# ee40_robot_final_p2.net
KiCad netlist of a schematic drawn in EAGLE
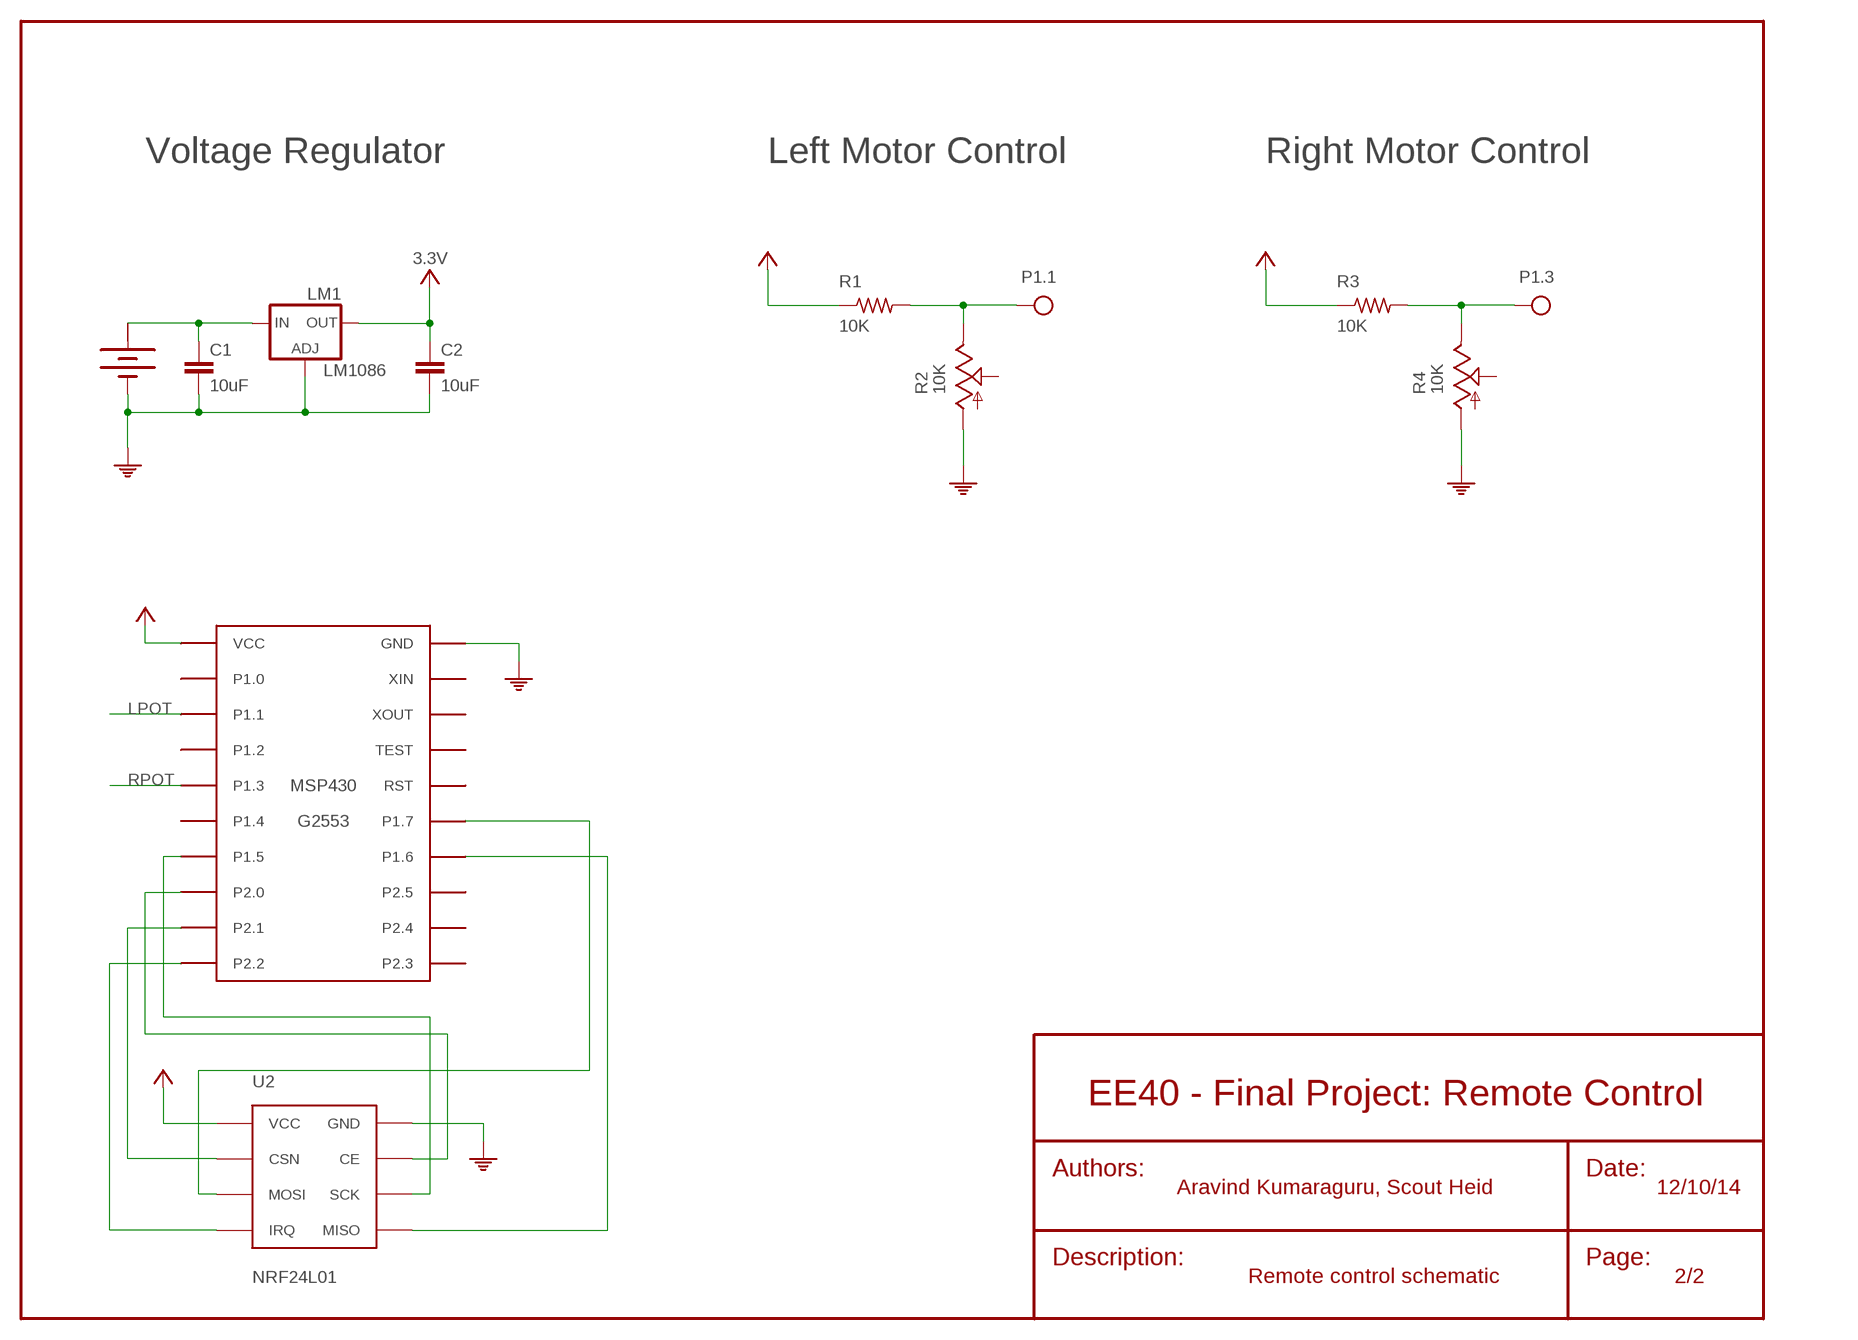
[diagram p0: schematic, sheet 1]

(export (version "E")
  (design (tool "Eeschema 10.0.6"))
  (components
    (comp (ref "BAT1")
      (value "9V D-CELL")
      (footprint "eagle-import:BATTERY")
      (libsource (lib "eagle-import") (part "BATTERY"))
    )
    (comp (ref "C1")
      (value "10uF")
      (footprint "eagle-import:C5B2.5")
      (libsource (lib "eagle-import") (part "C5/2.5"))
    )
    (comp (ref "C2")
      (value "10uF")
      (footprint "eagle-import:C5B2.5")
      (libsource (lib "eagle-import") (part "C5/2.5"))
    )
    (comp (ref "LM1")
      (value "LM1086")
      (footprint "eagle-import:TO220L1")
      (libsource (lib "eagle-import") (part "LM138-TL"))
    )
    (comp (ref "R1")
      (value "10K")
      (footprint "eagle-import:VMTA55")
      (libsource (lib "eagle-import") (part "R-US_VMTA55"))
    )
    (comp (ref "R2")
      (value "10K")
      (footprint "eagle-import:RJ9W")
      (libsource (lib "eagle-import") (part "TRIM_US-RJ9W"))
    )
    (comp (ref "R3")
      (value "10K")
      (footprint "eagle-import:VMTA55")
      (libsource (lib "eagle-import") (part "R-US_VMTA55"))
    )
    (comp (ref "R4")
      (value "10K")
      (footprint "eagle-import:RJ9W")
      (libsource (lib "eagle-import") (part "TRIM_US-RJ9W"))
    )
    (comp (ref "U1")
      (value "MSP430")
      (footprint "eagle-import:MSP430")
      (libsource (lib "eagle-import") (part "MSP430"))
    )
    (comp (ref "U2")
      (value "NRF24L01")
      (footprint "eagle-import:NRF24L01")
      (libsource (lib "eagle-import") (part "NRF24L01"))
    )
  )
  (nets
    (net (code "1") (name "/+") (class "Default")
      (node (ref "BAT1") (pin "+@1") (pinfunction "+_+@1") (pintype "power_in"))
    )
    (net (code "2") (name "3.3V") (class "Default")
      (node (ref "C2") (pin "1") (pinfunction "1_1") (pintype "passive"))
      (node (ref "LM1") (pin "2") (pinfunction "OUT_2") (pintype "passive"))
      (node (ref "R1") (pin "1") (pinfunction "1_1") (pintype "passive"))
      (node (ref "R3") (pin "1") (pinfunction "1_1") (pintype "passive"))
      (node (ref "U1") (pin "P$1") (pinfunction "VCC_P$1") (pintype "bidirectional"))
      (node (ref "U2") (pin "P$8") (pinfunction "VCC_P$8") (pintype "bidirectional"))
    )
    (net (code "3") (name "Net-(LM1-IN)") (class "Default")
      (node (ref "BAT1") (pin "+") (pinfunction "+_+") (pintype "power_in"))
      (node (ref "C1") (pin "1") (pinfunction "1_1") (pintype "passive"))
      (node (ref "LM1") (pin "3") (pinfunction "IN_3") (pintype "input"))
    )
    (net (code "4") (name "Net-(U1-P1.5)") (class "Default")
      (node (ref "U1") (pin "P$7") (pinfunction "P1.5_P$7") (pintype "bidirectional"))
      (node (ref "U2") (pin "P$7") (pinfunction "SCK_P$7") (pintype "bidirectional"))
    )
    (net (code "5") (name "Net-(U1-P1.6)") (class "Default")
      (node (ref "U1") (pin "P$14") (pinfunction "P1.6_P$14") (pintype "bidirectional"))
      (node (ref "U2") (pin "P$5") (pinfunction "MISO_P$5") (pintype "bidirectional"))
    )
    (net (code "6") (name "Net-(U1-P1.7)") (class "Default")
      (node (ref "U1") (pin "P$15") (pinfunction "P1.7_P$15") (pintype "bidirectional"))
      (node (ref "U2") (pin "P$6") (pinfunction "MOSI_P$6") (pintype "bidirectional"))
    )
    (net (code "7") (name "Net-(U1-P2.0)") (class "Default")
      (node (ref "U1") (pin "P$8") (pinfunction "P2.0_P$8") (pintype "bidirectional"))
      (node (ref "U2") (pin "P$1") (pinfunction "CE_P$1") (pintype "bidirectional"))
    )
    (net (code "8") (name "Net-(U1-P2.1)") (class "Default")
      (node (ref "U1") (pin "P$9") (pinfunction "P2.1_P$9") (pintype "bidirectional"))
      (node (ref "U2") (pin "P$2") (pinfunction "CSN_P$2") (pintype "bidirectional"))
    )
    (net (code "9") (name "Net-(U1-P2.2)") (class "Default")
      (node (ref "U1") (pin "P$10") (pinfunction "P2.2_P$10") (pintype "bidirectional"))
      (node (ref "U2") (pin "P$4") (pinfunction "IRQ_P$4") (pintype "bidirectional"))
    )
    (net (code "10") (name "P1.1") (class "Default")
      (node (ref "R1") (pin "2") (pinfunction "2_2") (pintype "passive"))
      (node (ref "R2") (pin "E") (pinfunction "E_E") (pintype "passive"))
      (node (ref "U1") (pin "P$3") (pinfunction "P1.1_P$3") (pintype "bidirectional"))
    )
    (net (code "11") (name "P1.3") (class "Default")
      (node (ref "R3") (pin "2") (pinfunction "2_2") (pintype "passive"))
      (node (ref "R4") (pin "E") (pinfunction "E_E") (pintype "passive"))
      (node (ref "U1") (pin "P$5") (pinfunction "P1.3_P$5") (pintype "bidirectional"))
    )
    (net (code "12") (name "PE") (class "Default")
      (node (ref "BAT1") (pin "-") (pinfunction "-_-") (pintype "power_in"))
      (node (ref "C1") (pin "2") (pinfunction "2_2") (pintype "passive"))
      (node (ref "C2") (pin "2") (pinfunction "2_2") (pintype "passive"))
      (node (ref "LM1") (pin "1") (pinfunction "ADJ_1") (pintype "input"))
      (node (ref "R2") (pin "A") (pinfunction "A_A") (pintype "passive"))
      (node (ref "R4") (pin "A") (pinfunction "A_A") (pintype "passive"))
      (node (ref "U1") (pin "P$20") (pinfunction "GND_P$20") (pintype "bidirectional"))
      (node (ref "U2") (pin "P$3") (pinfunction "GND_P$3") (pintype "bidirectional"))
    )
    (net (code "13") (name "unconnected-(R2-PadS)") (class "Default")
      (node (ref "R2") (pin "S") (pinfunction "S_S") (pintype "passive"))
    )
    (net (code "14") (name "unconnected-(R4-PadS)") (class "Default")
      (node (ref "R4") (pin "S") (pinfunction "S_S") (pintype "passive"))
    )
    (net (code "15") (name "unconnected-(U1-P1.0-PadP$2)") (class "Default")
      (node (ref "U1") (pin "P$2") (pinfunction "P1.0_P$2") (pintype "bidirectional"))
    )
    (net (code "16") (name "unconnected-(U1-P1.2-PadP$4)") (class "Default")
      (node (ref "U1") (pin "P$4") (pinfunction "P1.2_P$4") (pintype "bidirectional"))
    )
    (net (code "17") (name "unconnected-(U1-P1.4-PadP$6)") (class "Default")
      (node (ref "U1") (pin "P$6") (pinfunction "P1.4_P$6") (pintype "bidirectional"))
    )
    (net (code "18") (name "unconnected-(U1-P2.3-PadP$11)") (class "Default")
      (node (ref "U1") (pin "P$11") (pinfunction "P2.3_P$11") (pintype "bidirectional"))
    )
    (net (code "19") (name "unconnected-(U1-P2.4-PadP$12)") (class "Default")
      (node (ref "U1") (pin "P$12") (pinfunction "P2.4_P$12") (pintype "bidirectional"))
    )
    (net (code "20") (name "unconnected-(U1-P2.5-PadP$13)") (class "Default")
      (node (ref "U1") (pin "P$13") (pinfunction "P2.5_P$13") (pintype "bidirectional"))
    )
    (net (code "21") (name "unconnected-(U1-RST-PadP$16)") (class "Default")
      (node (ref "U1") (pin "P$16") (pinfunction "RST_P$16") (pintype "bidirectional"))
    )
    (net (code "22") (name "unconnected-(U1-TEST-PadP$17)") (class "Default")
      (node (ref "U1") (pin "P$17") (pinfunction "TEST_P$17") (pintype "bidirectional"))
    )
    (net (code "23") (name "unconnected-(U1-XIN-PadP$19)") (class "Default")
      (node (ref "U1") (pin "P$19") (pinfunction "XIN_P$19") (pintype "bidirectional"))
    )
    (net (code "24") (name "unconnected-(U1-XOUT-PadP$18)") (class "Default")
      (node (ref "U1") (pin "P$18") (pinfunction "XOUT_P$18") (pintype "bidirectional"))
    )
  )
)
